# IRComms.net
KiCad netlist of a schematic drawn in Altium Designer
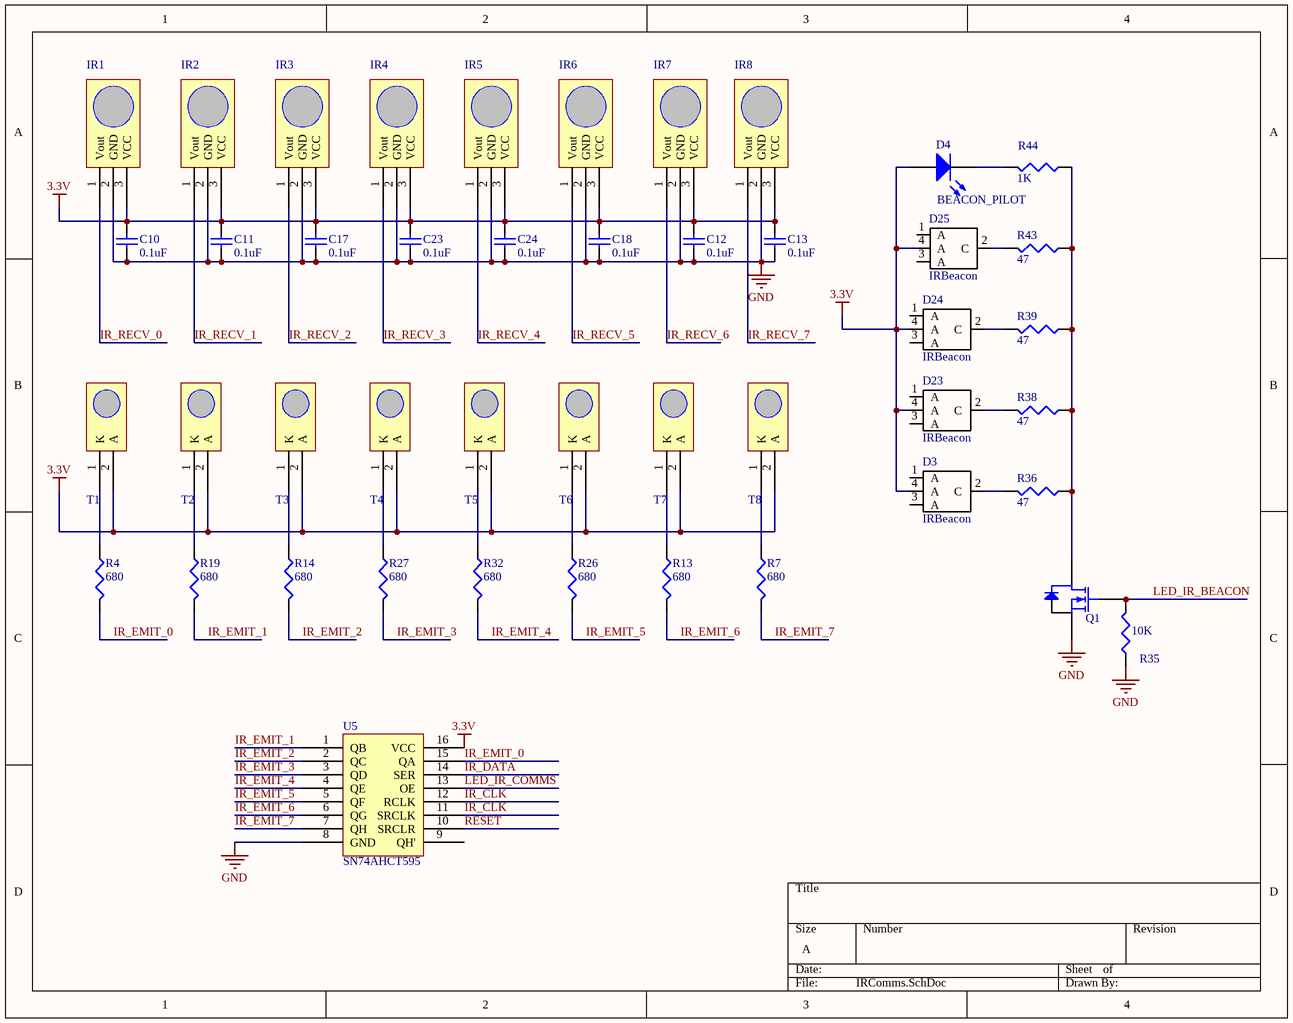
[diagram p0: IRComms.SchDoc]

(export (version "E")
  (design (tool "Eeschema 10.0.6"))
  (components
    (comp (ref "C10")
      (value "0.1uF")
      (footprint "CAPC1005L")
      (description "Capacitor (Semiconductor SIM Model)")
      (fields (field (name "Comment") "Cap Semi") (field (name "PUBLISHER") "Altium Limited"))
      (libsource (lib "Miscellaneous Devices") (part "Cap Semi"))
    )
    (comp (ref "C11")
      (value "0.1uF")
      (footprint "CAPC1005L")
      (description "Capacitor (Semiconductor SIM Model)")
      (fields (field (name "Comment") "Cap Semi") (field (name "PUBLISHER") "Altium Limited"))
      (libsource (lib "Miscellaneous Devices") (part "Cap Semi"))
    )
    (comp (ref "C12")
      (value "0.1uF")
      (footprint "CAPC1005L")
      (description "Capacitor (Semiconductor SIM Model)")
      (fields (field (name "Comment") "Cap Semi") (field (name "PUBLISHER") "Altium Limited"))
      (libsource (lib "Miscellaneous Devices") (part "Cap Semi"))
    )
    (comp (ref "C13")
      (value "0.1uF")
      (footprint "CAPC1005L")
      (description "Capacitor (Semiconductor SIM Model)")
      (fields (field (name "Comment") "Cap Semi") (field (name "PUBLISHER") "Altium Limited"))
      (libsource (lib "Miscellaneous Devices") (part "Cap Semi"))
    )
    (comp (ref "C17")
      (value "0.1uF")
      (footprint "CAPC1005L")
      (description "Capacitor (Semiconductor SIM Model)")
      (fields (field (name "Comment") "Cap Semi") (field (name "PUBLISHER") "Altium Limited"))
      (libsource (lib "Miscellaneous Devices") (part "Cap Semi"))
    )
    (comp (ref "C18")
      (value "0.1uF")
      (footprint "CAPC1005L")
      (description "Capacitor (Semiconductor SIM Model)")
      (fields (field (name "Comment") "Cap Semi") (field (name "PUBLISHER") "Altium Limited"))
      (libsource (lib "Miscellaneous Devices") (part "Cap Semi"))
    )
    (comp (ref "C23")
      (value "0.1uF")
      (footprint "CAPC1005L")
      (description "Capacitor (Semiconductor SIM Model)")
      (fields (field (name "Comment") "Cap Semi") (field (name "PUBLISHER") "Altium Limited"))
      (libsource (lib "Miscellaneous Devices") (part "Cap Semi"))
    )
    (comp (ref "C24")
      (value "0.1uF")
      (footprint "CAPC1005L")
      (description "Capacitor (Semiconductor SIM Model)")
      (fields (field (name "Comment") "Cap Semi") (field (name "PUBLISHER") "Altium Limited"))
      (libsource (lib "Miscellaneous Devices") (part "Cap Semi"))
    )
    (comp (ref "D3") (value "IRBeacon") (footprint "IRBeacon") (libsource (lib "mrone") (part "IRBeacon")))
    (comp (ref "D4")
      (value "BEACON_PILOT")
      (footprint "SurfaceMount(603)")
      (libsource (lib "mrone") (part "LED"))
    )
    (comp (ref "D23") (value "IRBeacon") (footprint "IRBeacon") (libsource (lib "mrone") (part "IRBeacon")))
    (comp (ref "D24") (value "IRBeacon") (footprint "IRBeacon") (libsource (lib "mrone") (part "IRBeacon")))
    (comp (ref "D25") (value "IRBeacon") (footprint "IRBeacon") (libsource (lib "mrone") (part "IRBeacon")))
    (comp (ref "IR1")
      (value "GP1UX31QS")
      (footprint "GP1UX31QS")
      (libsource (lib "mrone") (part "GP1UX31QS"))
    )
    (comp (ref "IR2")
      (value "GP1UX31QS")
      (footprint "GP1UX31QS")
      (libsource (lib "mrone") (part "GP1UX31QS"))
    )
    (comp (ref "IR3")
      (value "GP1UX31QS")
      (footprint "GP1UX31QS")
      (libsource (lib "mrone") (part "GP1UX31QS"))
    )
    (comp (ref "IR4")
      (value "GP1UX31QS")
      (footprint "GP1UX31QS")
      (libsource (lib "mrone") (part "GP1UX31QS"))
    )
    (comp (ref "IR5")
      (value "GP1UX31QS")
      (footprint "GP1UX31QS")
      (libsource (lib "mrone") (part "GP1UX31QS"))
    )
    (comp (ref "IR6")
      (value "GP1UX31QS")
      (footprint "GP1UX31QS")
      (libsource (lib "mrone") (part "GP1UX31QS"))
    )
    (comp (ref "IR7")
      (value "GP1UX31QS")
      (footprint "GP1UX31QS")
      (libsource (lib "mrone") (part "GP1UX31QS"))
    )
    (comp (ref "IR8")
      (value "GP1UX31QS")
      (footprint "GP1UX31QS")
      (libsource (lib "mrone") (part "GP1UX31QS"))
    )
    (comp (ref "Q1") (value "Mosfet") (footprint "SOT-23") (libsource (lib "mrone") (part "Mosfet")))
    (comp (ref "R4")
      (value "680")
      (footprint "RESC1608L")
      (description "Resistor")
      (fields (field (name "Comment") "Res3") (field (name "PUBLISHER") "Altium Limited"))
      (libsource (lib "Miscellaneous Devices") (part "Res3"))
    )
    (comp (ref "R7")
      (value "680")
      (footprint "RESC1608L")
      (description "Resistor")
      (fields (field (name "Comment") "Res3") (field (name "PUBLISHER") "Altium Limited"))
      (libsource (lib "Miscellaneous Devices") (part "Res3"))
    )
    (comp (ref "R13")
      (value "680")
      (footprint "RESC1608L")
      (description "Resistor")
      (fields (field (name "Comment") "Res3") (field (name "PUBLISHER") "Altium Limited"))
      (libsource (lib "Miscellaneous Devices") (part "Res3"))
    )
    (comp (ref "R14")
      (value "680")
      (footprint "RESC1608L")
      (description "Resistor")
      (fields (field (name "Comment") "Res3") (field (name "PUBLISHER") "Altium Limited"))
      (libsource (lib "Miscellaneous Devices") (part "Res3"))
    )
    (comp (ref "R19")
      (value "680")
      (footprint "RESC1608L")
      (description "Resistor")
      (fields (field (name "Comment") "Res3") (field (name "PUBLISHER") "Altium Limited"))
      (libsource (lib "Miscellaneous Devices") (part "Res3"))
    )
    (comp (ref "R26")
      (value "680")
      (footprint "RESC1608L")
      (description "Resistor")
      (fields (field (name "Comment") "Res3") (field (name "PUBLISHER") "Altium Limited"))
      (libsource (lib "Miscellaneous Devices") (part "Res3"))
    )
    (comp (ref "R27")
      (value "680")
      (footprint "RESC1608L")
      (description "Resistor")
      (fields (field (name "Comment") "Res3") (field (name "PUBLISHER") "Altium Limited"))
      (libsource (lib "Miscellaneous Devices") (part "Res3"))
    )
    (comp (ref "R32")
      (value "680")
      (footprint "RESC1608L")
      (description "Resistor")
      (fields (field (name "Comment") "Res3") (field (name "PUBLISHER") "Altium Limited"))
      (libsource (lib "Miscellaneous Devices") (part "Res3"))
    )
    (comp (ref "R35")
      (value "10K")
      (footprint "RESC1608L")
      (description "Resistor")
      (fields (field (name "Comment") "Res3") (field (name "PUBLISHER") "Altium Limited"))
      (libsource (lib "Miscellaneous Devices") (part "Res3"))
    )
    (comp (ref "R36")
      (value "47")
      (footprint "RESC1608L")
      (description "Resistor")
      (fields (field (name "Comment") "Res3") (field (name "PUBLISHER") "Altium Limited"))
      (libsource (lib "Miscellaneous Devices") (part "Res3"))
    )
    (comp (ref "R38")
      (value "47")
      (footprint "RESC1608L")
      (description "Resistor")
      (fields (field (name "Comment") "Res3") (field (name "PUBLISHER") "Altium Limited"))
      (libsource (lib "Miscellaneous Devices") (part "Res3"))
    )
    (comp (ref "R39")
      (value "47")
      (footprint "RESC1608L")
      (description "Resistor")
      (fields (field (name "Comment") "Res3") (field (name "PUBLISHER") "Altium Limited"))
      (libsource (lib "Miscellaneous Devices") (part "Res3"))
    )
    (comp (ref "R43")
      (value "47")
      (footprint "RESC1608L")
      (description "Resistor")
      (fields (field (name "Comment") "Res3") (field (name "PUBLISHER") "Altium Limited"))
      (libsource (lib "Miscellaneous Devices") (part "Res3"))
    )
    (comp (ref "R44")
      (value "1K")
      (footprint "RESC1608L")
      (description "Resistor")
      (fields (field (name "Comment") "Res3") (field (name "PUBLISHER") "Altium Limited"))
      (libsource (lib "Miscellaneous Devices") (part "Res3"))
    )
    (comp (ref "T1") (value "LN54") (footprint "LN54") (libsource (lib "mrone") (part "LN54")))
    (comp (ref "T2") (value "LN54") (footprint "LN54") (libsource (lib "mrone") (part "LN54")))
    (comp (ref "T3") (value "LN54") (footprint "LN54") (libsource (lib "mrone") (part "LN54")))
    (comp (ref "T4") (value "LN54") (footprint "LN54") (libsource (lib "mrone") (part "LN54")))
    (comp (ref "T5") (value "LN54") (footprint "LN54") (libsource (lib "mrone") (part "LN54")))
    (comp (ref "T6") (value "LN54") (footprint "LN54") (libsource (lib "mrone") (part "LN54")))
    (comp (ref "T7") (value "LN54") (footprint "LN54") (libsource (lib "mrone") (part "LN54")))
    (comp (ref "T8") (value "LN54") (footprint "LN54") (libsource (lib "mrone") (part "LN54")))
    (comp (ref "U5")
      (value "SN74AHCT595")
      (footprint "TSOP65P640X120-16N")
      (libsource (lib "mrone") (part "SN74AHCT595_Shift_Register"))
    )
  )
  (nets
    (net (code "1") (name "/IR_CLK") (class "Default")
      (node (ref "U5") (pin "11") (pinfunction "SRCLK_11") (pintype "passive"))
      (node (ref "U5") (pin "12") (pinfunction "RCLK_12") (pintype "passive"))
    )
    (net (code "2") (name "/IR_DATA") (class "Default")
      (node (ref "U5") (pin "14") (pinfunction "SER_14") (pintype "passive"))
    )
    (net (code "3") (name "/IR_EMIT_0") (class "Default")
      (node (ref "R4") (pin "2") (pinfunction "2_2") (pintype "passive"))
      (node (ref "U5") (pin "15") (pinfunction "QA_15") (pintype "passive"))
    )
    (net (code "4") (name "/IR_EMIT_1") (class "Default")
      (node (ref "R19") (pin "2") (pinfunction "2_2") (pintype "passive"))
      (node (ref "U5") (pin "1") (pinfunction "QB_1") (pintype "passive"))
    )
    (net (code "5") (name "/IR_EMIT_2") (class "Default")
      (node (ref "R14") (pin "2") (pinfunction "2_2") (pintype "passive"))
      (node (ref "U5") (pin "2") (pinfunction "QC_2") (pintype "passive"))
    )
    (net (code "6") (name "/IR_EMIT_3") (class "Default")
      (node (ref "R27") (pin "2") (pinfunction "2_2") (pintype "passive"))
      (node (ref "U5") (pin "3") (pinfunction "QD_3") (pintype "passive"))
    )
    (net (code "7") (name "/IR_EMIT_4") (class "Default")
      (node (ref "R32") (pin "2") (pinfunction "2_2") (pintype "passive"))
      (node (ref "U5") (pin "4") (pinfunction "QE_4") (pintype "passive"))
    )
    (net (code "8") (name "/IR_EMIT_5") (class "Default")
      (node (ref "R26") (pin "2") (pinfunction "2_2") (pintype "passive"))
      (node (ref "U5") (pin "5") (pinfunction "QF_5") (pintype "passive"))
    )
    (net (code "9") (name "/IR_EMIT_6") (class "Default")
      (node (ref "R13") (pin "2") (pinfunction "2_2") (pintype "passive"))
      (node (ref "U5") (pin "6") (pinfunction "QG_6") (pintype "passive"))
    )
    (net (code "10") (name "/IR_EMIT_7") (class "Default")
      (node (ref "R7") (pin "2") (pinfunction "2_2") (pintype "passive"))
      (node (ref "U5") (pin "7") (pinfunction "QH_7") (pintype "passive"))
    )
    (net (code "11") (name "/IR_RECV_0") (class "Default")
      (node (ref "IR1") (pin "1") (pinfunction "Vout_1") (pintype "passive"))
    )
    (net (code "12") (name "/IR_RECV_1") (class "Default")
      (node (ref "IR2") (pin "1") (pinfunction "Vout_1") (pintype "passive"))
    )
    (net (code "13") (name "/IR_RECV_2") (class "Default")
      (node (ref "IR3") (pin "1") (pinfunction "Vout_1") (pintype "passive"))
    )
    (net (code "14") (name "/IR_RECV_3") (class "Default")
      (node (ref "IR4") (pin "1") (pinfunction "Vout_1") (pintype "passive"))
    )
    (net (code "15") (name "/IR_RECV_4") (class "Default")
      (node (ref "IR5") (pin "1") (pinfunction "Vout_1") (pintype "passive"))
    )
    (net (code "16") (name "/IR_RECV_5") (class "Default")
      (node (ref "IR6") (pin "1") (pinfunction "Vout_1") (pintype "passive"))
    )
    (net (code "17") (name "/IR_RECV_6") (class "Default")
      (node (ref "IR7") (pin "1") (pinfunction "Vout_1") (pintype "passive"))
    )
    (net (code "18") (name "/IR_RECV_7") (class "Default")
      (node (ref "IR8") (pin "1") (pinfunction "Vout_1") (pintype "passive"))
    )
    (net (code "19") (name "/LED_IR_BEACON") (class "Default")
      (node (ref "Q1") (pin "1") (pinfunction "G_1") (pintype "passive"))
      (node (ref "R35") (pin "2") (pinfunction "2_2") (pintype "passive"))
    )
    (net (code "20") (name "/LED_IR_COMMS") (class "Default")
      (node (ref "U5") (pin "13") (pinfunction "OE_13") (pintype "passive"))
    )
    (net (code "21") (name "/RESET") (class "Default")
      (node (ref "U5") (pin "10") (pinfunction "SRCLR_10") (pintype "passive"))
    )
    (net (code "22") (name "3.3V") (class "Default")
      (node (ref "C10") (pin "2") (pinfunction "2_2") (pintype "passive"))
      (node (ref "C11") (pin "2") (pinfunction "2_2") (pintype "passive"))
      (node (ref "C12") (pin "2") (pinfunction "2_2") (pintype "passive"))
      (node (ref "C13") (pin "2") (pinfunction "2_2") (pintype "passive"))
      (node (ref "C17") (pin "2") (pinfunction "2_2") (pintype "passive"))
      (node (ref "C18") (pin "2") (pinfunction "2_2") (pintype "passive"))
      (node (ref "C23") (pin "2") (pinfunction "2_2") (pintype "passive"))
      (node (ref "C24") (pin "2") (pinfunction "2_2") (pintype "passive"))
      (node (ref "D23") (pin "4") (pinfunction "A_4") (pintype "passive"))
      (node (ref "D24") (pin "4") (pinfunction "A_4") (pintype "passive"))
      (node (ref "D25") (pin "4") (pinfunction "A_4") (pintype "passive"))
      (node (ref "D3") (pin "4") (pinfunction "A_4") (pintype "passive"))
      (node (ref "D4") (pin "1") (pinfunction "A_1") (pintype "passive"))
      (node (ref "IR1") (pin "3") (pinfunction "VCC_3") (pintype "power_in"))
      (node (ref "IR2") (pin "3") (pinfunction "VCC_3") (pintype "power_in"))
      (node (ref "IR3") (pin "3") (pinfunction "VCC_3") (pintype "power_in"))
      (node (ref "IR4") (pin "3") (pinfunction "VCC_3") (pintype "power_in"))
      (node (ref "IR5") (pin "3") (pinfunction "VCC_3") (pintype "power_in"))
      (node (ref "IR6") (pin "3") (pinfunction "VCC_3") (pintype "power_in"))
      (node (ref "IR7") (pin "3") (pinfunction "VCC_3") (pintype "power_in"))
      (node (ref "IR8") (pin "3") (pinfunction "VCC_3") (pintype "power_in"))
      (node (ref "T1") (pin "2") (pinfunction "A_2") (pintype "passive"))
      (node (ref "T2") (pin "2") (pinfunction "A_2") (pintype "passive"))
      (node (ref "T3") (pin "2") (pinfunction "A_2") (pintype "passive"))
      (node (ref "T4") (pin "2") (pinfunction "A_2") (pintype "passive"))
      (node (ref "T5") (pin "2") (pinfunction "A_2") (pintype "passive"))
      (node (ref "T6") (pin "2") (pinfunction "A_2") (pintype "passive"))
      (node (ref "T7") (pin "2") (pinfunction "A_2") (pintype "passive"))
      (node (ref "T8") (pin "2") (pinfunction "A_2") (pintype "passive"))
      (node (ref "U5") (pin "16") (pinfunction "VCC_16") (pintype "passive"))
    )
    (net (code "23") (name "GND") (class "Default")
      (node (ref "C10") (pin "1") (pinfunction "1_1") (pintype "passive"))
      (node (ref "C11") (pin "1") (pinfunction "1_1") (pintype "passive"))
      (node (ref "C12") (pin "1") (pinfunction "1_1") (pintype "passive"))
      (node (ref "C13") (pin "1") (pinfunction "1_1") (pintype "passive"))
      (node (ref "C17") (pin "1") (pinfunction "1_1") (pintype "passive"))
      (node (ref "C18") (pin "1") (pinfunction "1_1") (pintype "passive"))
      (node (ref "C23") (pin "1") (pinfunction "1_1") (pintype "passive"))
      (node (ref "C24") (pin "1") (pinfunction "1_1") (pintype "passive"))
      (node (ref "IR1") (pin "2") (pinfunction "GND_2") (pintype "power_in"))
      (node (ref "IR2") (pin "2") (pinfunction "GND_2") (pintype "power_in"))
      (node (ref "IR3") (pin "2") (pinfunction "GND_2") (pintype "power_in"))
      (node (ref "IR4") (pin "2") (pinfunction "GND_2") (pintype "power_in"))
      (node (ref "IR5") (pin "2") (pinfunction "GND_2") (pintype "power_in"))
      (node (ref "IR6") (pin "2") (pinfunction "GND_2") (pintype "power_in"))
      (node (ref "IR7") (pin "2") (pinfunction "GND_2") (pintype "power_in"))
      (node (ref "IR8") (pin "2") (pinfunction "GND_2") (pintype "power_in"))
      (node (ref "Q1") (pin "2") (pinfunction "S_2") (pintype "passive"))
      (node (ref "R35") (pin "1") (pinfunction "1_1") (pintype "passive"))
      (node (ref "U5") (pin "8") (pinfunction "GND_8") (pintype "passive"))
    )
    (net (code "24") (name "Net-(D3-C)") (class "Default")
      (node (ref "D3") (pin "2") (pinfunction "C_2") (pintype "passive"))
      (node (ref "R36") (pin "2") (pinfunction "2_2") (pintype "passive"))
    )
    (net (code "25") (name "Net-(D4-K)") (class "Default")
      (node (ref "D4") (pin "2") (pinfunction "K_2") (pintype "passive"))
      (node (ref "R44") (pin "2") (pinfunction "2_2") (pintype "passive"))
    )
    (net (code "26") (name "Net-(D23-C)") (class "Default")
      (node (ref "D23") (pin "2") (pinfunction "C_2") (pintype "passive"))
      (node (ref "R38") (pin "2") (pinfunction "2_2") (pintype "passive"))
    )
    (net (code "27") (name "Net-(D24-C)") (class "Default")
      (node (ref "D24") (pin "2") (pinfunction "C_2") (pintype "passive"))
      (node (ref "R39") (pin "2") (pinfunction "2_2") (pintype "passive"))
    )
    (net (code "28") (name "Net-(D25-C)") (class "Default")
      (node (ref "D25") (pin "2") (pinfunction "C_2") (pintype "passive"))
      (node (ref "R43") (pin "2") (pinfunction "2_2") (pintype "passive"))
    )
    (net (code "29") (name "Net-(Q1-D)") (class "Default")
      (node (ref "Q1") (pin "3") (pinfunction "D_3") (pintype "passive"))
      (node (ref "R36") (pin "1") (pinfunction "1_1") (pintype "passive"))
      (node (ref "R38") (pin "1") (pinfunction "1_1") (pintype "passive"))
      (node (ref "R39") (pin "1") (pinfunction "1_1") (pintype "passive"))
      (node (ref "R43") (pin "1") (pinfunction "1_1") (pintype "passive"))
      (node (ref "R44") (pin "1") (pinfunction "1_1") (pintype "passive"))
    )
    (net (code "30") (name "Net-(T1-K)") (class "Default")
      (node (ref "R4") (pin "1") (pinfunction "1_1") (pintype "passive"))
      (node (ref "T1") (pin "1") (pinfunction "K_1") (pintype "passive"))
    )
    (net (code "31") (name "Net-(T2-K)") (class "Default")
      (node (ref "R19") (pin "1") (pinfunction "1_1") (pintype "passive"))
      (node (ref "T2") (pin "1") (pinfunction "K_1") (pintype "passive"))
    )
    (net (code "32") (name "Net-(T3-K)") (class "Default")
      (node (ref "R14") (pin "1") (pinfunction "1_1") (pintype "passive"))
      (node (ref "T3") (pin "1") (pinfunction "K_1") (pintype "passive"))
    )
    (net (code "33") (name "Net-(T4-K)") (class "Default")
      (node (ref "R27") (pin "1") (pinfunction "1_1") (pintype "passive"))
      (node (ref "T4") (pin "1") (pinfunction "K_1") (pintype "passive"))
    )
    (net (code "34") (name "Net-(T5-K)") (class "Default")
      (node (ref "R32") (pin "1") (pinfunction "1_1") (pintype "passive"))
      (node (ref "T5") (pin "1") (pinfunction "K_1") (pintype "passive"))
    )
    (net (code "35") (name "Net-(T6-K)") (class "Default")
      (node (ref "R26") (pin "1") (pinfunction "1_1") (pintype "passive"))
      (node (ref "T6") (pin "1") (pinfunction "K_1") (pintype "passive"))
    )
    (net (code "36") (name "Net-(T7-K)") (class "Default")
      (node (ref "R13") (pin "1") (pinfunction "1_1") (pintype "passive"))
      (node (ref "T7") (pin "1") (pinfunction "K_1") (pintype "passive"))
    )
    (net (code "37") (name "Net-(T8-K)") (class "Default")
      (node (ref "R7") (pin "1") (pinfunction "1_1") (pintype "passive"))
      (node (ref "T8") (pin "1") (pinfunction "K_1") (pintype "passive"))
    )
    (net (code "38") (name "unconnected-(D3-A-Pad1)") (class "Default")
      (node (ref "D3") (pin "1") (pinfunction "A_1") (pintype "passive"))
    )
    (net (code "39") (name "unconnected-(D3-A-Pad3)") (class "Default")
      (node (ref "D3") (pin "3") (pinfunction "A_3") (pintype "passive"))
    )
    (net (code "40") (name "unconnected-(D23-A-Pad1)") (class "Default")
      (node (ref "D23") (pin "1") (pinfunction "A_1") (pintype "passive"))
    )
    (net (code "41") (name "unconnected-(D23-A-Pad3)") (class "Default")
      (node (ref "D23") (pin "3") (pinfunction "A_3") (pintype "passive"))
    )
    (net (code "42") (name "unconnected-(D24-A-Pad1)") (class "Default")
      (node (ref "D24") (pin "1") (pinfunction "A_1") (pintype "passive"))
    )
    (net (code "43") (name "unconnected-(D24-A-Pad3)") (class "Default")
      (node (ref "D24") (pin "3") (pinfunction "A_3") (pintype "passive"))
    )
    (net (code "44") (name "unconnected-(D25-A-Pad1)") (class "Default")
      (node (ref "D25") (pin "1") (pinfunction "A_1") (pintype "passive"))
    )
    (net (code "45") (name "unconnected-(D25-A-Pad3)") (class "Default")
      (node (ref "D25") (pin "3") (pinfunction "A_3") (pintype "passive"))
    )
    (net (code "46") (name "unconnected-(U5-QH'-Pad9)") (class "Default")
      (node (ref "U5") (pin "9") (pinfunction "QH'_9") (pintype "passive"))
    )
  )
)
